# t.net
KiCad netlist of a schematic drawn in EAGLE
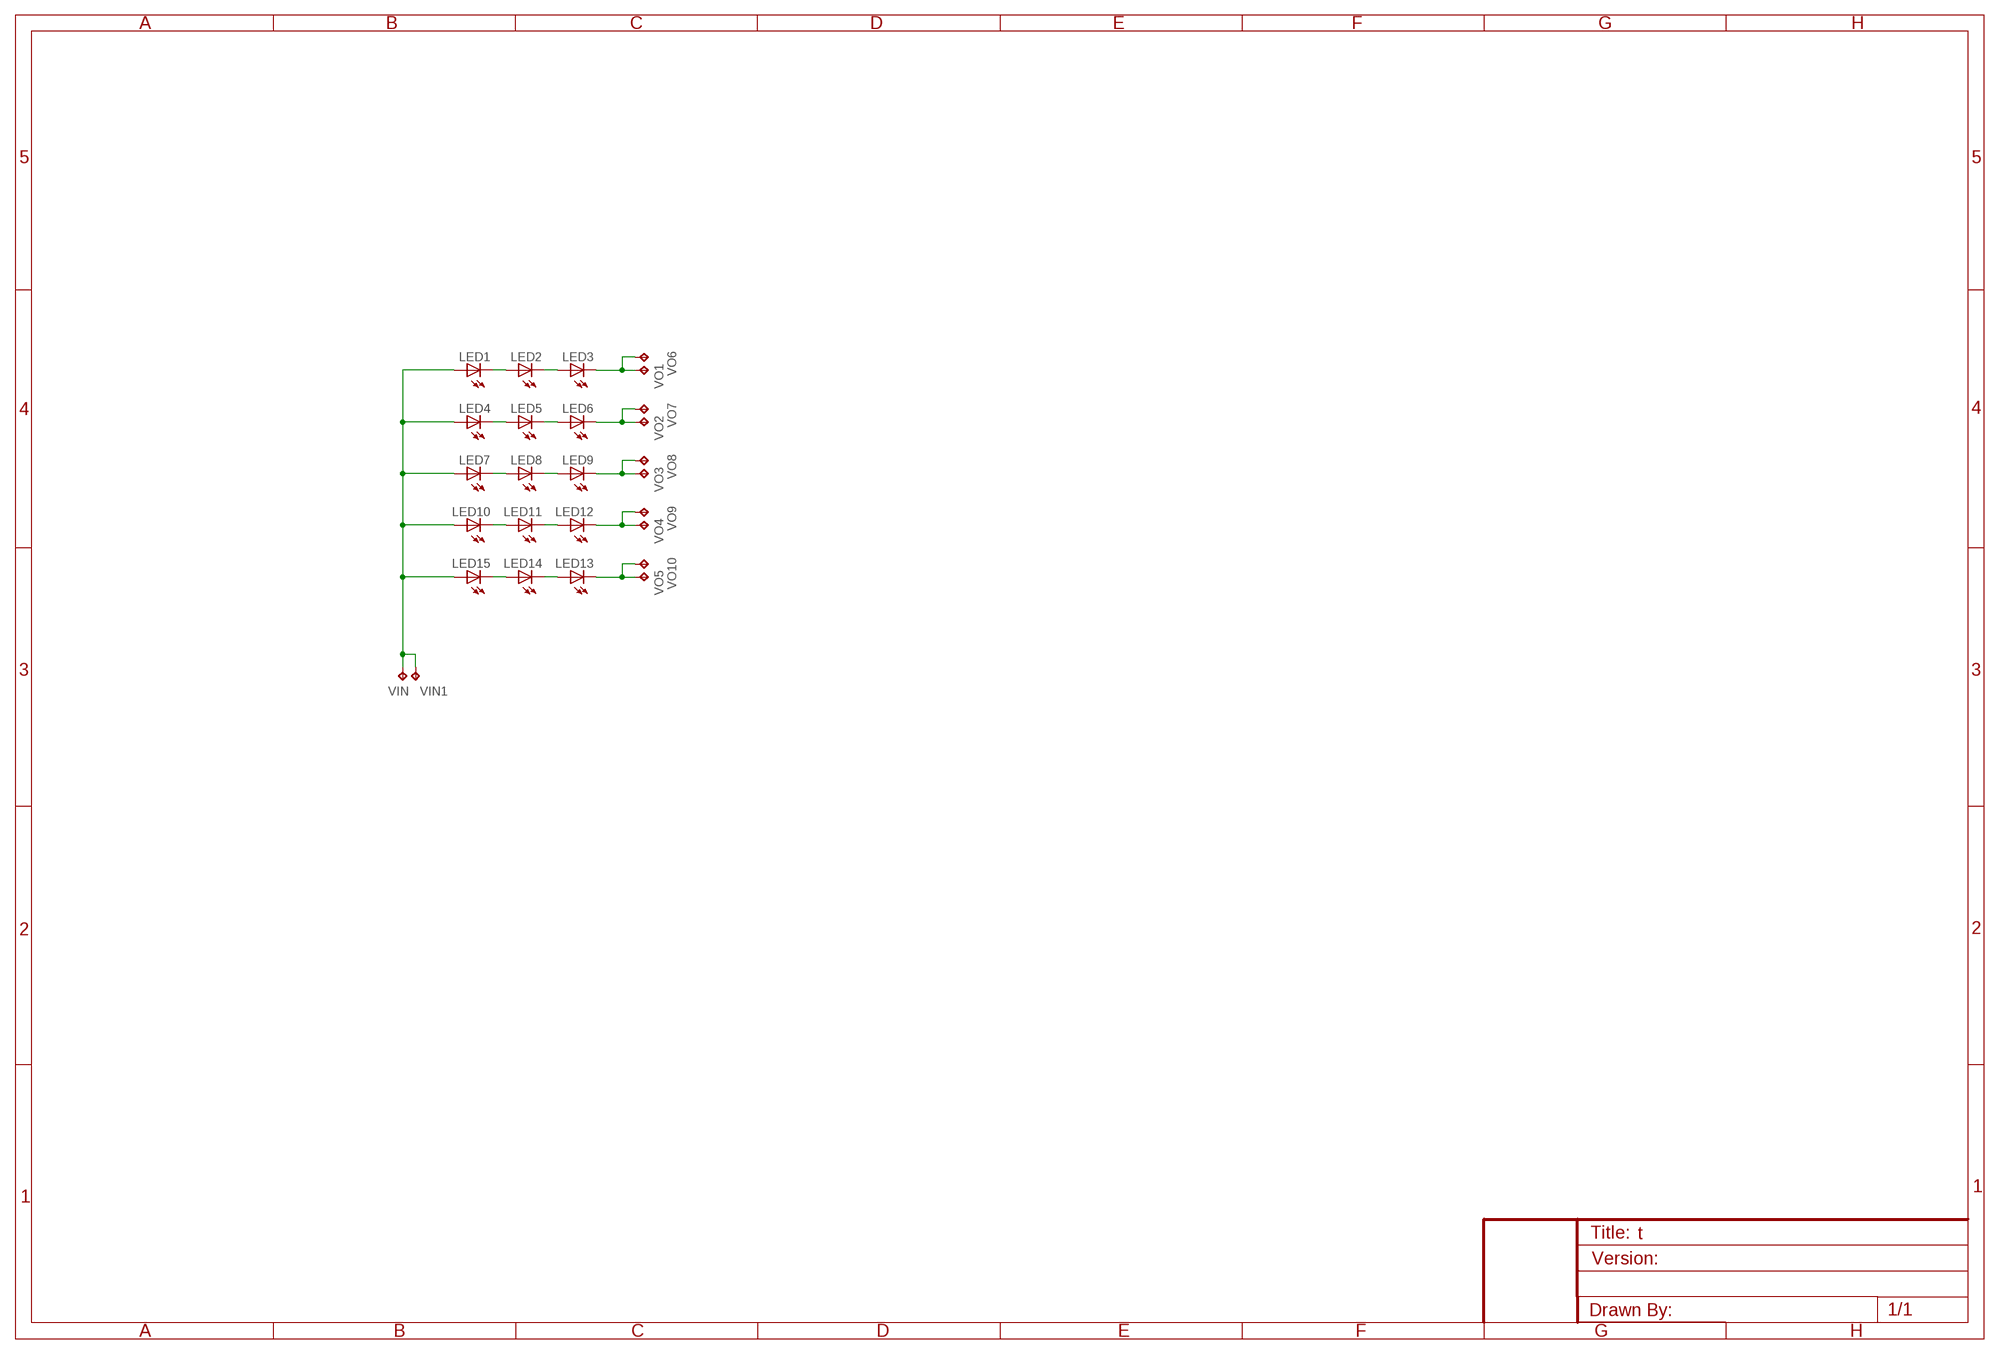
[diagram p0: schematic, sheet 1]

(export (version "E")
  (design (tool "Eeschema 10.0.6"))
  (components
    (comp (ref "LED1")
      (value "LED0805")
      (footprint "eagle-import:LED_0805")
      (libsource (lib "eagle-import") (part "LED0805"))
    )
    (comp (ref "LED2")
      (value "LED0805")
      (footprint "eagle-import:LED_0805")
      (libsource (lib "eagle-import") (part "LED0805"))
    )
    (comp (ref "LED3")
      (value "LED0805")
      (footprint "eagle-import:LED_0805")
      (libsource (lib "eagle-import") (part "LED0805"))
    )
    (comp (ref "LED4")
      (value "LED0805")
      (footprint "eagle-import:LED_0805")
      (libsource (lib "eagle-import") (part "LED0805"))
    )
    (comp (ref "LED5")
      (value "LED0805")
      (footprint "eagle-import:LED_0805")
      (libsource (lib "eagle-import") (part "LED0805"))
    )
    (comp (ref "LED6")
      (value "LED0805")
      (footprint "eagle-import:LED_0805")
      (libsource (lib "eagle-import") (part "LED0805"))
    )
    (comp (ref "LED7")
      (value "LED0805")
      (footprint "eagle-import:LED_0805")
      (libsource (lib "eagle-import") (part "LED0805"))
    )
    (comp (ref "LED8")
      (value "LED0805")
      (footprint "eagle-import:LED_0805")
      (libsource (lib "eagle-import") (part "LED0805"))
    )
    (comp (ref "LED9")
      (value "LED0805")
      (footprint "eagle-import:LED_0805")
      (libsource (lib "eagle-import") (part "LED0805"))
    )
    (comp (ref "LED10")
      (value "LED0805")
      (footprint "eagle-import:LED_0805")
      (libsource (lib "eagle-import") (part "LED0805"))
    )
    (comp (ref "LED11")
      (value "LED0805")
      (footprint "eagle-import:LED_0805")
      (libsource (lib "eagle-import") (part "LED0805"))
    )
    (comp (ref "LED12")
      (value "LED0805")
      (footprint "eagle-import:LED_0805")
      (libsource (lib "eagle-import") (part "LED0805"))
    )
    (comp (ref "LED13")
      (value "LED0805")
      (footprint "eagle-import:LED_0805")
      (libsource (lib "eagle-import") (part "LED0805"))
    )
    (comp (ref "LED14")
      (value "LED0805")
      (footprint "eagle-import:LED_0805")
      (libsource (lib "eagle-import") (part "LED0805"))
    )
    (comp (ref "LED15")
      (value "LED0805")
      (footprint "eagle-import:LED_0805")
      (libsource (lib "eagle-import") (part "LED0805"))
    )
    (comp (ref "VIN")
      (value "TEST_POINTPAD1-20")
      (footprint "eagle-import:P1-20")
      (libsource (lib "eagle-import") (part "TEST_POINTPAD1-20"))
    )
    (comp (ref "VIN1")
      (value "TEST_POINTPAD1-20")
      (footprint "eagle-import:P1-20")
      (libsource (lib "eagle-import") (part "TEST_POINTPAD1-20"))
    )
    (comp (ref "VO1")
      (value "TEST_POINTPAD1-20")
      (footprint "eagle-import:P1-20")
      (libsource (lib "eagle-import") (part "TEST_POINTPAD1-20"))
    )
    (comp (ref "VO2")
      (value "TEST_POINTPAD1-20")
      (footprint "eagle-import:P1-20")
      (libsource (lib "eagle-import") (part "TEST_POINTPAD1-20"))
    )
    (comp (ref "VO3")
      (value "TEST_POINTPAD1-20")
      (footprint "eagle-import:P1-20")
      (libsource (lib "eagle-import") (part "TEST_POINTPAD1-20"))
    )
    (comp (ref "VO4")
      (value "TEST_POINTPAD1-20")
      (footprint "eagle-import:P1-20")
      (libsource (lib "eagle-import") (part "TEST_POINTPAD1-20"))
    )
    (comp (ref "VO5")
      (value "TEST_POINTPAD1-20")
      (footprint "eagle-import:P1-20")
      (libsource (lib "eagle-import") (part "TEST_POINTPAD1-20"))
    )
    (comp (ref "VO6")
      (value "TEST_POINTPAD1-20")
      (footprint "eagle-import:P1-20")
      (libsource (lib "eagle-import") (part "TEST_POINTPAD1-20"))
    )
    (comp (ref "VO7")
      (value "TEST_POINTPAD1-20")
      (footprint "eagle-import:P1-20")
      (libsource (lib "eagle-import") (part "TEST_POINTPAD1-20"))
    )
    (comp (ref "VO8")
      (value "TEST_POINTPAD1-20")
      (footprint "eagle-import:P1-20")
      (libsource (lib "eagle-import") (part "TEST_POINTPAD1-20"))
    )
    (comp (ref "VO9")
      (value "TEST_POINTPAD1-20")
      (footprint "eagle-import:P1-20")
      (libsource (lib "eagle-import") (part "TEST_POINTPAD1-20"))
    )
    (comp (ref "VO10")
      (value "TEST_POINTPAD1-20")
      (footprint "eagle-import:P1-20")
      (libsource (lib "eagle-import") (part "TEST_POINTPAD1-20"))
    )
  )
  (nets
    (net (code "1") (name "Net-(LED1-PadA)") (class "Default")
      (node (ref "LED1") (pin "A") (pinfunction "A_A") (pintype "passive"))
      (node (ref "LED10") (pin "A") (pinfunction "A_A") (pintype "passive"))
      (node (ref "LED15") (pin "A") (pinfunction "A_A") (pintype "passive"))
      (node (ref "LED4") (pin "A") (pinfunction "A_A") (pintype "passive"))
      (node (ref "LED7") (pin "A") (pinfunction "A_A") (pintype "passive"))
      (node (ref "VIN") (pin "TP") (pinfunction "TP_TP") (pintype "input"))
      (node (ref "VIN1") (pin "TP") (pinfunction "TP_TP") (pintype "input"))
    )
    (net (code "2") (name "Net-(LED1-PadC)") (class "Default")
      (node (ref "LED1") (pin "C") (pinfunction "C_C") (pintype "passive"))
      (node (ref "LED2") (pin "A") (pinfunction "A_A") (pintype "passive"))
    )
    (net (code "3") (name "Net-(LED2-PadC)") (class "Default")
      (node (ref "LED2") (pin "C") (pinfunction "C_C") (pintype "passive"))
      (node (ref "LED3") (pin "A") (pinfunction "A_A") (pintype "passive"))
    )
    (net (code "4") (name "Net-(LED3-PadC)") (class "Default")
      (node (ref "LED3") (pin "C") (pinfunction "C_C") (pintype "passive"))
      (node (ref "VO1") (pin "TP") (pinfunction "TP_TP") (pintype "input"))
      (node (ref "VO6") (pin "TP") (pinfunction "TP_TP") (pintype "input"))
    )
    (net (code "5") (name "Net-(LED4-PadC)") (class "Default")
      (node (ref "LED4") (pin "C") (pinfunction "C_C") (pintype "passive"))
      (node (ref "LED5") (pin "A") (pinfunction "A_A") (pintype "passive"))
    )
    (net (code "6") (name "Net-(LED5-PadC)") (class "Default")
      (node (ref "LED5") (pin "C") (pinfunction "C_C") (pintype "passive"))
      (node (ref "LED6") (pin "A") (pinfunction "A_A") (pintype "passive"))
    )
    (net (code "7") (name "Net-(LED6-PadC)") (class "Default")
      (node (ref "LED6") (pin "C") (pinfunction "C_C") (pintype "passive"))
      (node (ref "VO2") (pin "TP") (pinfunction "TP_TP") (pintype "input"))
      (node (ref "VO7") (pin "TP") (pinfunction "TP_TP") (pintype "input"))
    )
    (net (code "8") (name "Net-(LED7-PadC)") (class "Default")
      (node (ref "LED7") (pin "C") (pinfunction "C_C") (pintype "passive"))
      (node (ref "LED8") (pin "A") (pinfunction "A_A") (pintype "passive"))
    )
    (net (code "9") (name "Net-(LED8-PadC)") (class "Default")
      (node (ref "LED8") (pin "C") (pinfunction "C_C") (pintype "passive"))
      (node (ref "LED9") (pin "A") (pinfunction "A_A") (pintype "passive"))
    )
    (net (code "10") (name "Net-(LED9-PadC)") (class "Default")
      (node (ref "LED9") (pin "C") (pinfunction "C_C") (pintype "passive"))
      (node (ref "VO3") (pin "TP") (pinfunction "TP_TP") (pintype "input"))
      (node (ref "VO8") (pin "TP") (pinfunction "TP_TP") (pintype "input"))
    )
    (net (code "11") (name "Net-(LED10-PadC)") (class "Default")
      (node (ref "LED10") (pin "C") (pinfunction "C_C") (pintype "passive"))
      (node (ref "LED11") (pin "A") (pinfunction "A_A") (pintype "passive"))
    )
    (net (code "12") (name "Net-(LED11-PadC)") (class "Default")
      (node (ref "LED11") (pin "C") (pinfunction "C_C") (pintype "passive"))
      (node (ref "LED12") (pin "A") (pinfunction "A_A") (pintype "passive"))
    )
    (net (code "13") (name "Net-(LED12-PadC)") (class "Default")
      (node (ref "LED12") (pin "C") (pinfunction "C_C") (pintype "passive"))
      (node (ref "VO4") (pin "TP") (pinfunction "TP_TP") (pintype "input"))
      (node (ref "VO9") (pin "TP") (pinfunction "TP_TP") (pintype "input"))
    )
    (net (code "14") (name "Net-(LED13-PadA)") (class "Default")
      (node (ref "LED13") (pin "A") (pinfunction "A_A") (pintype "passive"))
      (node (ref "LED14") (pin "C") (pinfunction "C_C") (pintype "passive"))
    )
    (net (code "15") (name "Net-(LED13-PadC)") (class "Default")
      (node (ref "LED13") (pin "C") (pinfunction "C_C") (pintype "passive"))
      (node (ref "VO10") (pin "TP") (pinfunction "TP_TP") (pintype "input"))
      (node (ref "VO5") (pin "TP") (pinfunction "TP_TP") (pintype "input"))
    )
    (net (code "16") (name "Net-(LED14-PadA)") (class "Default")
      (node (ref "LED14") (pin "A") (pinfunction "A_A") (pintype "passive"))
      (node (ref "LED15") (pin "C") (pinfunction "C_C") (pintype "passive"))
    )
  )
)
